# SCH_ESP32-Head-Module_2024-04-16.net
KiCad netlist of a schematic drawn in EasyEDA
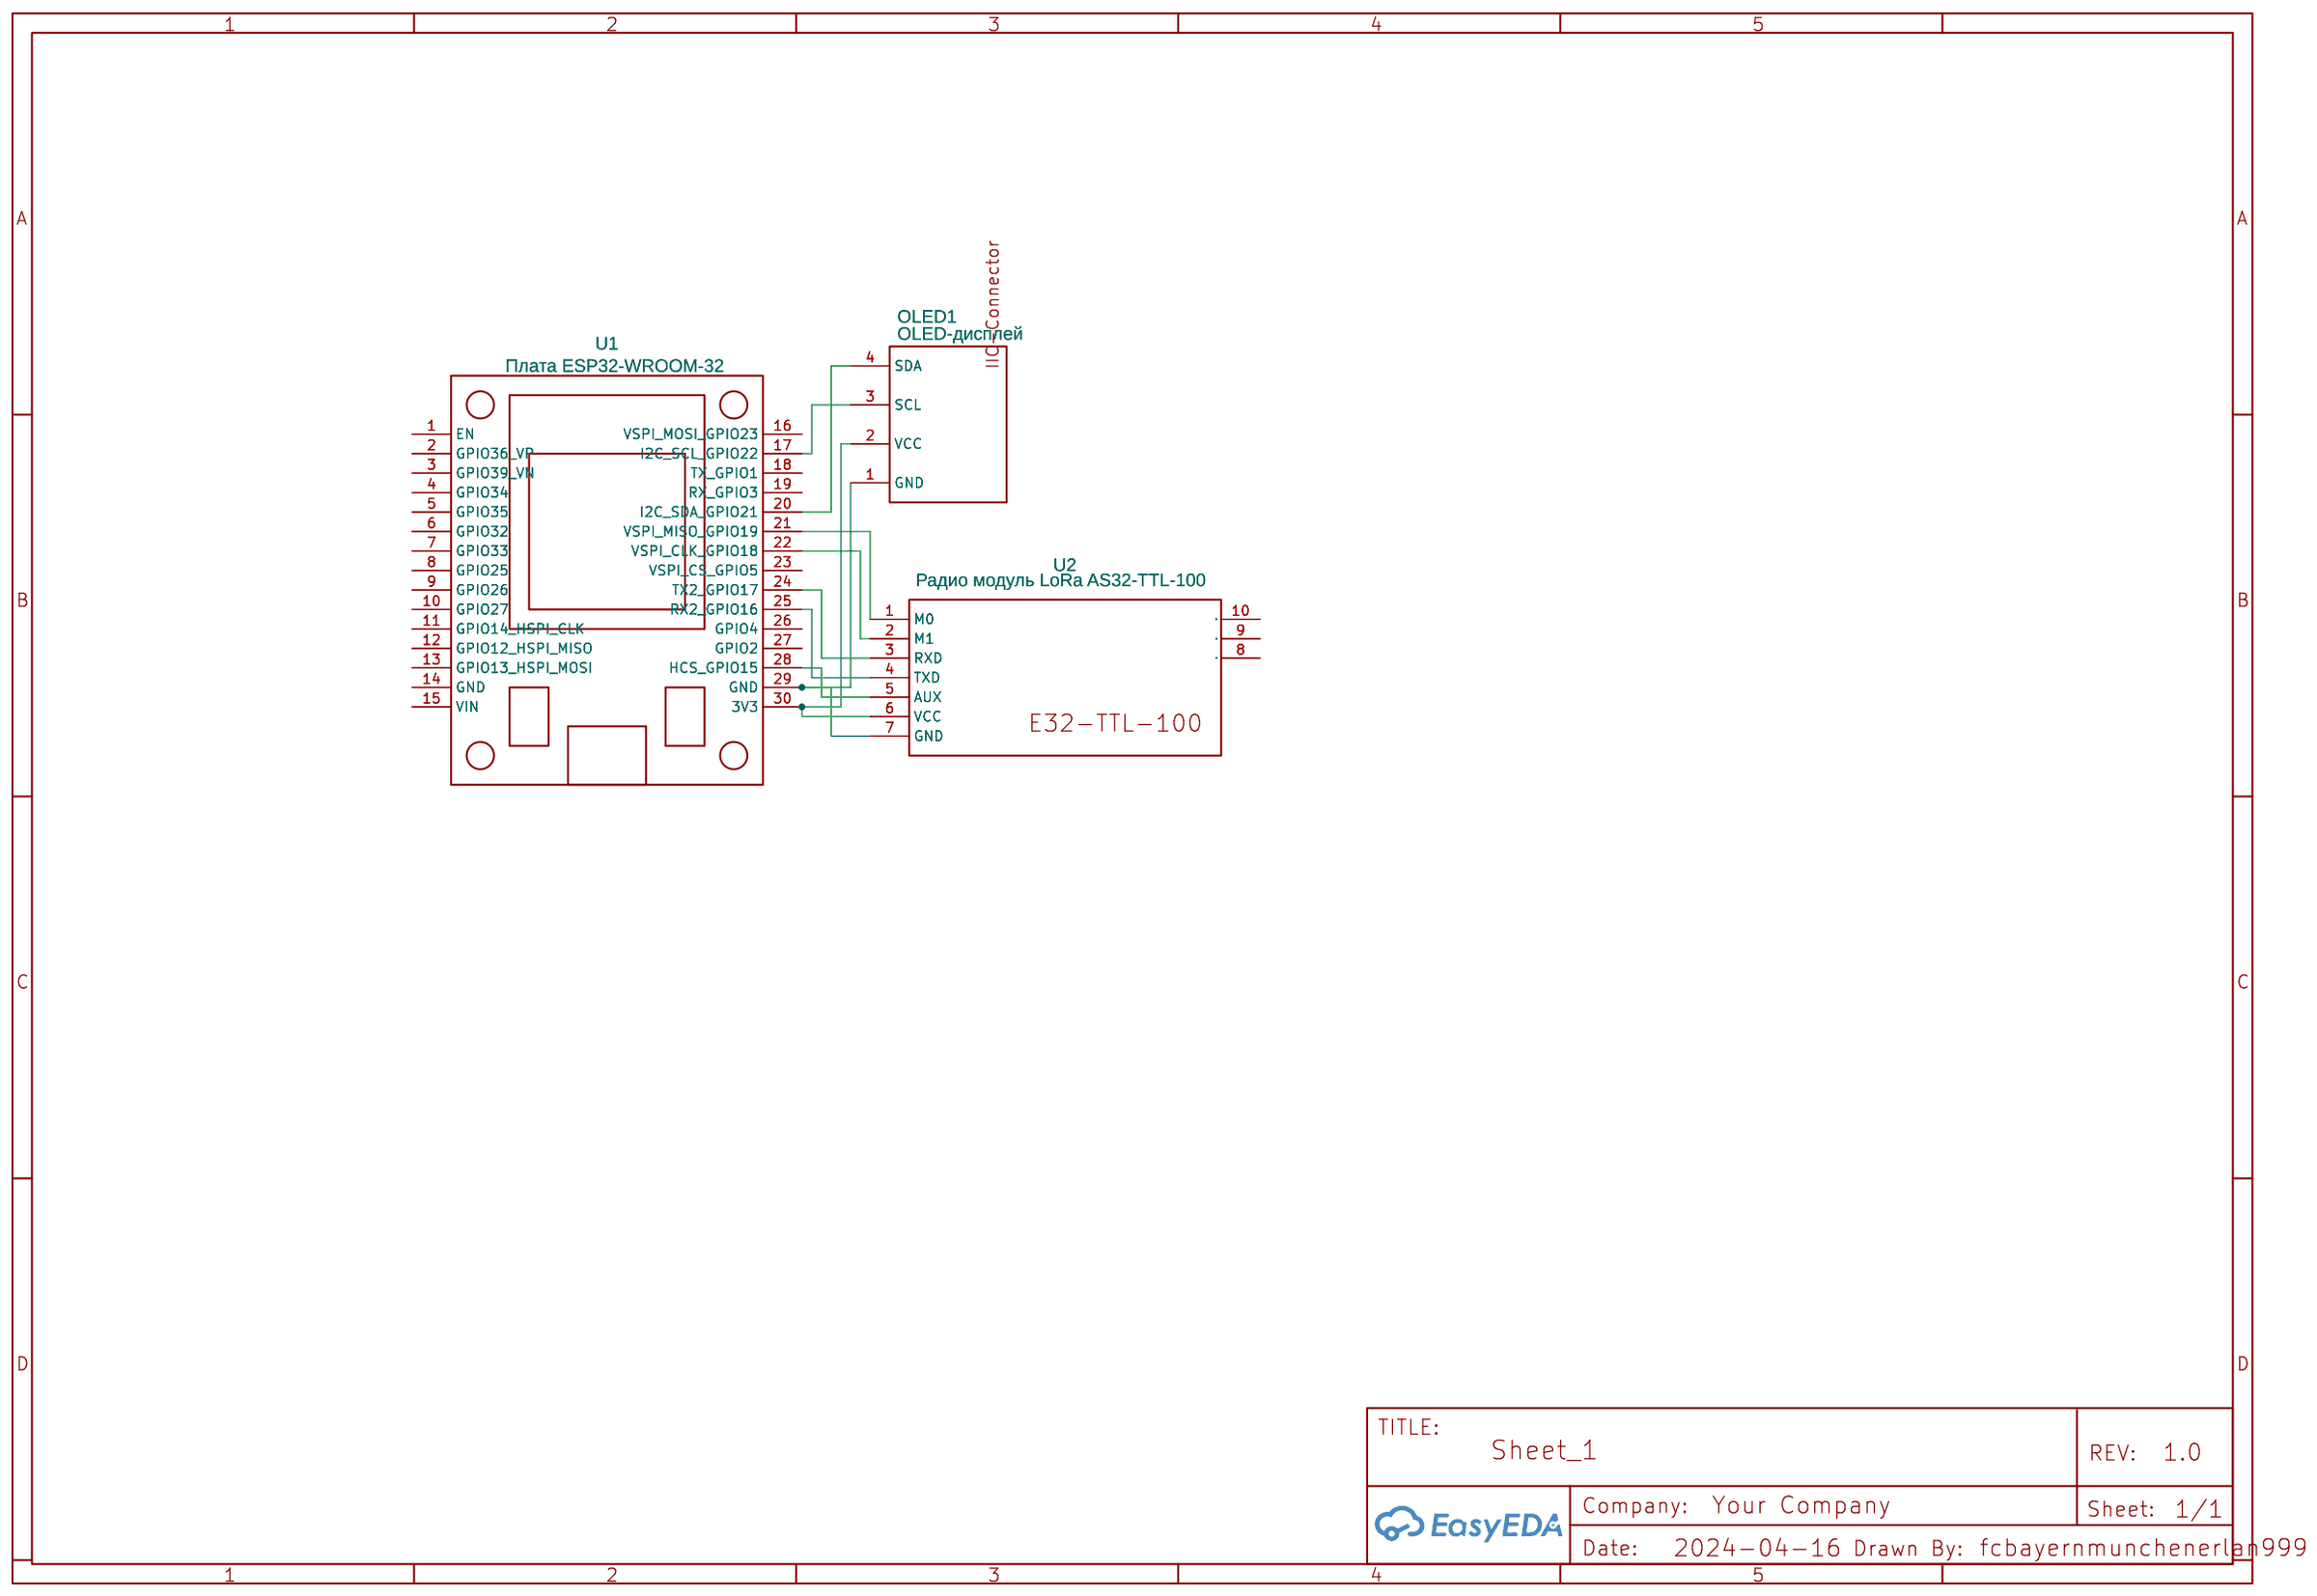
[diagram p0: schematic sheet]

(export (version "E")
  (design (tool "Eeschema 10.0.6"))
  (components
    (comp (ref "OLED1")
      (value "OLED-дисплей")
      (fields (field (name "Manufacturer Part") "0.96OLED_4P_MODULE_JX"))
      (libsource (lib "") (part "0.96OLED_4P_MODULE_JX"))
    )
    (comp (ref "U1") (value "Плата ESP32-WROOM-32") (libsource (lib "") (part "Плата ESP32 (вариант 2)")))
    (comp (ref "U2")
      (value "Радио модуль LoRa AS32-TTL-100")
      (fields (field (name "Manufacturer Part") "E32-433T20DC") (field (name "Manufacturer") "EBYTE(亿佰特)"))
      (libsource (lib "") (part "E32-TTL-100"))
    )
  )
  (nets
    (net (code "1") (name "Net-(OLED1-GND)") (class "Default")
      (node (ref "OLED1") (pin "1") (pinfunction "GND_1") (pintype "unspecified"))
      (node (ref "U1") (pin "29") (pinfunction "GND_29") (pintype "bidirectional"))
      (node (ref "U2") (pin "7") (pinfunction "GND_7") (pintype "unspecified"))
    )
    (net (code "2") (name "Net-(OLED1-SCL)") (class "Default")
      (node (ref "OLED1") (pin "3") (pinfunction "SCL_3") (pintype "unspecified"))
      (node (ref "U1") (pin "17") (pinfunction "I2C_SCL_GPIO22_17") (pintype "bidirectional"))
    )
    (net (code "3") (name "Net-(OLED1-SDA)") (class "Default")
      (node (ref "OLED1") (pin "4") (pinfunction "SDA_4") (pintype "unspecified"))
      (node (ref "U1") (pin "20") (pinfunction "I2C_SDA_GPIO21_20") (pintype "bidirectional"))
    )
    (net (code "4") (name "Net-(OLED1-VCC)") (class "Default")
      (node (ref "OLED1") (pin "2") (pinfunction "VCC_2") (pintype "unspecified"))
      (node (ref "U1") (pin "30") (pinfunction "3V3_30") (pintype "bidirectional"))
      (node (ref "U2") (pin "6") (pinfunction "VCC_6") (pintype "passive"))
    )
    (net (code "5") (name "Net-(U1-HCS_GPIO15)") (class "Default")
      (node (ref "U1") (pin "28") (pinfunction "HCS_GPIO15_28") (pintype "bidirectional"))
      (node (ref "U2") (pin "5") (pinfunction "AUX_5") (pintype "unspecified"))
    )
    (net (code "6") (name "Net-(U1-RX2_GPIO16)") (class "Default")
      (node (ref "U1") (pin "25") (pinfunction "RX2_GPIO16_25") (pintype "bidirectional"))
      (node (ref "U2") (pin "4") (pinfunction "TXD_4") (pintype "unspecified"))
    )
    (net (code "7") (name "Net-(U1-TX2_GPIO17)") (class "Default")
      (node (ref "U1") (pin "24") (pinfunction "TX2_GPIO17_24") (pintype "bidirectional"))
      (node (ref "U2") (pin "3") (pinfunction "RXD_3") (pintype "unspecified"))
    )
    (net (code "8") (name "Net-(U1-VSPI_CLK_GPIO18)") (class "Default")
      (node (ref "U1") (pin "22") (pinfunction "VSPI_CLK_GPIO18_22") (pintype "passive"))
      (node (ref "U2") (pin "2") (pinfunction "M1_2") (pintype "unspecified"))
    )
    (net (code "9") (name "Net-(U1-VSPI_MISO_GPIO19)") (class "Default")
      (node (ref "U1") (pin "21") (pinfunction "VSPI_MISO_GPIO19_21") (pintype "bidirectional"))
      (node (ref "U2") (pin "1") (pinfunction "M0_1") (pintype "unspecified"))
    )
    (net (code "10") (name "unconnected-(U1-EN-Pad1)") (class "Default")
      (node (ref "U1") (pin "1") (pinfunction "EN_1") (pintype "passive"))
    )
    (net (code "11") (name "unconnected-(U1-GND-Pad14)") (class "Default")
      (node (ref "U1") (pin "14") (pinfunction "GND_14") (pintype "passive"))
    )
    (net (code "12") (name "unconnected-(U1-GPIO2-Pad27)") (class "Default")
      (node (ref "U1") (pin "27") (pinfunction "GPIO2_27") (pintype "bidirectional"))
    )
    (net (code "13") (name "unconnected-(U1-GPIO4-Pad26)") (class "Default")
      (node (ref "U1") (pin "26") (pinfunction "GPIO4_26") (pintype "bidirectional"))
    )
    (net (code "14") (name "unconnected-(U1-GPIO12_HSPI_MISO-Pad12)") (class "Default")
      (node (ref "U1") (pin "12") (pinfunction "GPIO12_HSPI_MISO_12") (pintype "bidirectional"))
    )
    (net (code "15") (name "unconnected-(U1-GPIO13_HSPI_MOSI-Pad13)") (class "Default")
      (node (ref "U1") (pin "13") (pinfunction "GPIO13_HSPI_MOSI_13") (pintype "bidirectional"))
    )
    (net (code "16") (name "unconnected-(U1-GPIO14_HSPI_CLK-Pad11)") (class "Default")
      (node (ref "U1") (pin "11") (pinfunction "GPIO14_HSPI_CLK_11") (pintype "bidirectional"))
    )
    (net (code "17") (name "unconnected-(U1-GPIO25-Pad8)") (class "Default")
      (node (ref "U1") (pin "8") (pinfunction "GPIO25_8") (pintype "bidirectional"))
    )
    (net (code "18") (name "unconnected-(U1-GPIO26-Pad9)") (class "Default")
      (node (ref "U1") (pin "9") (pinfunction "GPIO26_9") (pintype "bidirectional"))
    )
    (net (code "19") (name "unconnected-(U1-GPIO27-Pad10)") (class "Default")
      (node (ref "U1") (pin "10") (pinfunction "GPIO27_10") (pintype "bidirectional"))
    )
    (net (code "20") (name "unconnected-(U1-GPIO32-Pad6)") (class "Default")
      (node (ref "U1") (pin "6") (pinfunction "GPIO32_6") (pintype "bidirectional"))
    )
    (net (code "21") (name "unconnected-(U1-GPIO33-Pad7)") (class "Default")
      (node (ref "U1") (pin "7") (pinfunction "GPIO33_7") (pintype "bidirectional"))
    )
    (net (code "22") (name "unconnected-(U1-GPIO34-Pad4)") (class "Default")
      (node (ref "U1") (pin "4") (pinfunction "GPIO34_4") (pintype "bidirectional"))
    )
    (net (code "23") (name "unconnected-(U1-GPIO35-Pad5)") (class "Default")
      (node (ref "U1") (pin "5") (pinfunction "GPIO35_5") (pintype "bidirectional"))
    )
    (net (code "24") (name "unconnected-(U1-GPIO36_VP-Pad2)") (class "Default")
      (node (ref "U1") (pin "2") (pinfunction "GPIO36_VP_2") (pintype "bidirectional"))
    )
    (net (code "25") (name "unconnected-(U1-GPIO39_VN-Pad3)") (class "Default")
      (node (ref "U1") (pin "3") (pinfunction "GPIO39_VN_3") (pintype "bidirectional"))
    )
    (net (code "26") (name "unconnected-(U1-RX_GPIO3-Pad19)") (class "Default")
      (node (ref "U1") (pin "19") (pinfunction "RX_GPIO3_19") (pintype "bidirectional"))
    )
    (net (code "27") (name "unconnected-(U1-TX_GPIO1-Pad18)") (class "Default")
      (node (ref "U1") (pin "18") (pinfunction "TX_GPIO1_18") (pintype "bidirectional"))
    )
    (net (code "28") (name "unconnected-(U1-VIN-Pad15)") (class "Default")
      (node (ref "U1") (pin "15") (pinfunction "VIN_15") (pintype "bidirectional"))
    )
    (net (code "29") (name "unconnected-(U1-VSPI_CS_GPIO5-Pad23)") (class "Default")
      (node (ref "U1") (pin "23") (pinfunction "VSPI_CS_GPIO5_23") (pintype "bidirectional"))
    )
    (net (code "30") (name "unconnected-(U1-VSPI_MOSI_GPIO23-Pad16)") (class "Default")
      (node (ref "U1") (pin "16") (pinfunction "VSPI_MOSI_GPIO23_16") (pintype "passive"))
    )
    (net (code "31") (name "unconnected-(U2-Pad8)") (class "Default")
      (node (ref "U2") (pin "8") (pinfunction "8_8") (pintype "unspecified"))
    )
    (net (code "32") (name "unconnected-(U2-Pad9)") (class "Default")
      (node (ref "U2") (pin "9") (pinfunction "9_9") (pintype "unspecified"))
    )
    (net (code "33") (name "unconnected-(U2-Pad10)") (class "Default")
      (node (ref "U2") (pin "10") (pinfunction "10_10") (pintype "unspecified"))
    )
  )
)
